# WIFI-NightLight-Infinity.net
KiCad netlist of a schematic drawn in EAGLE
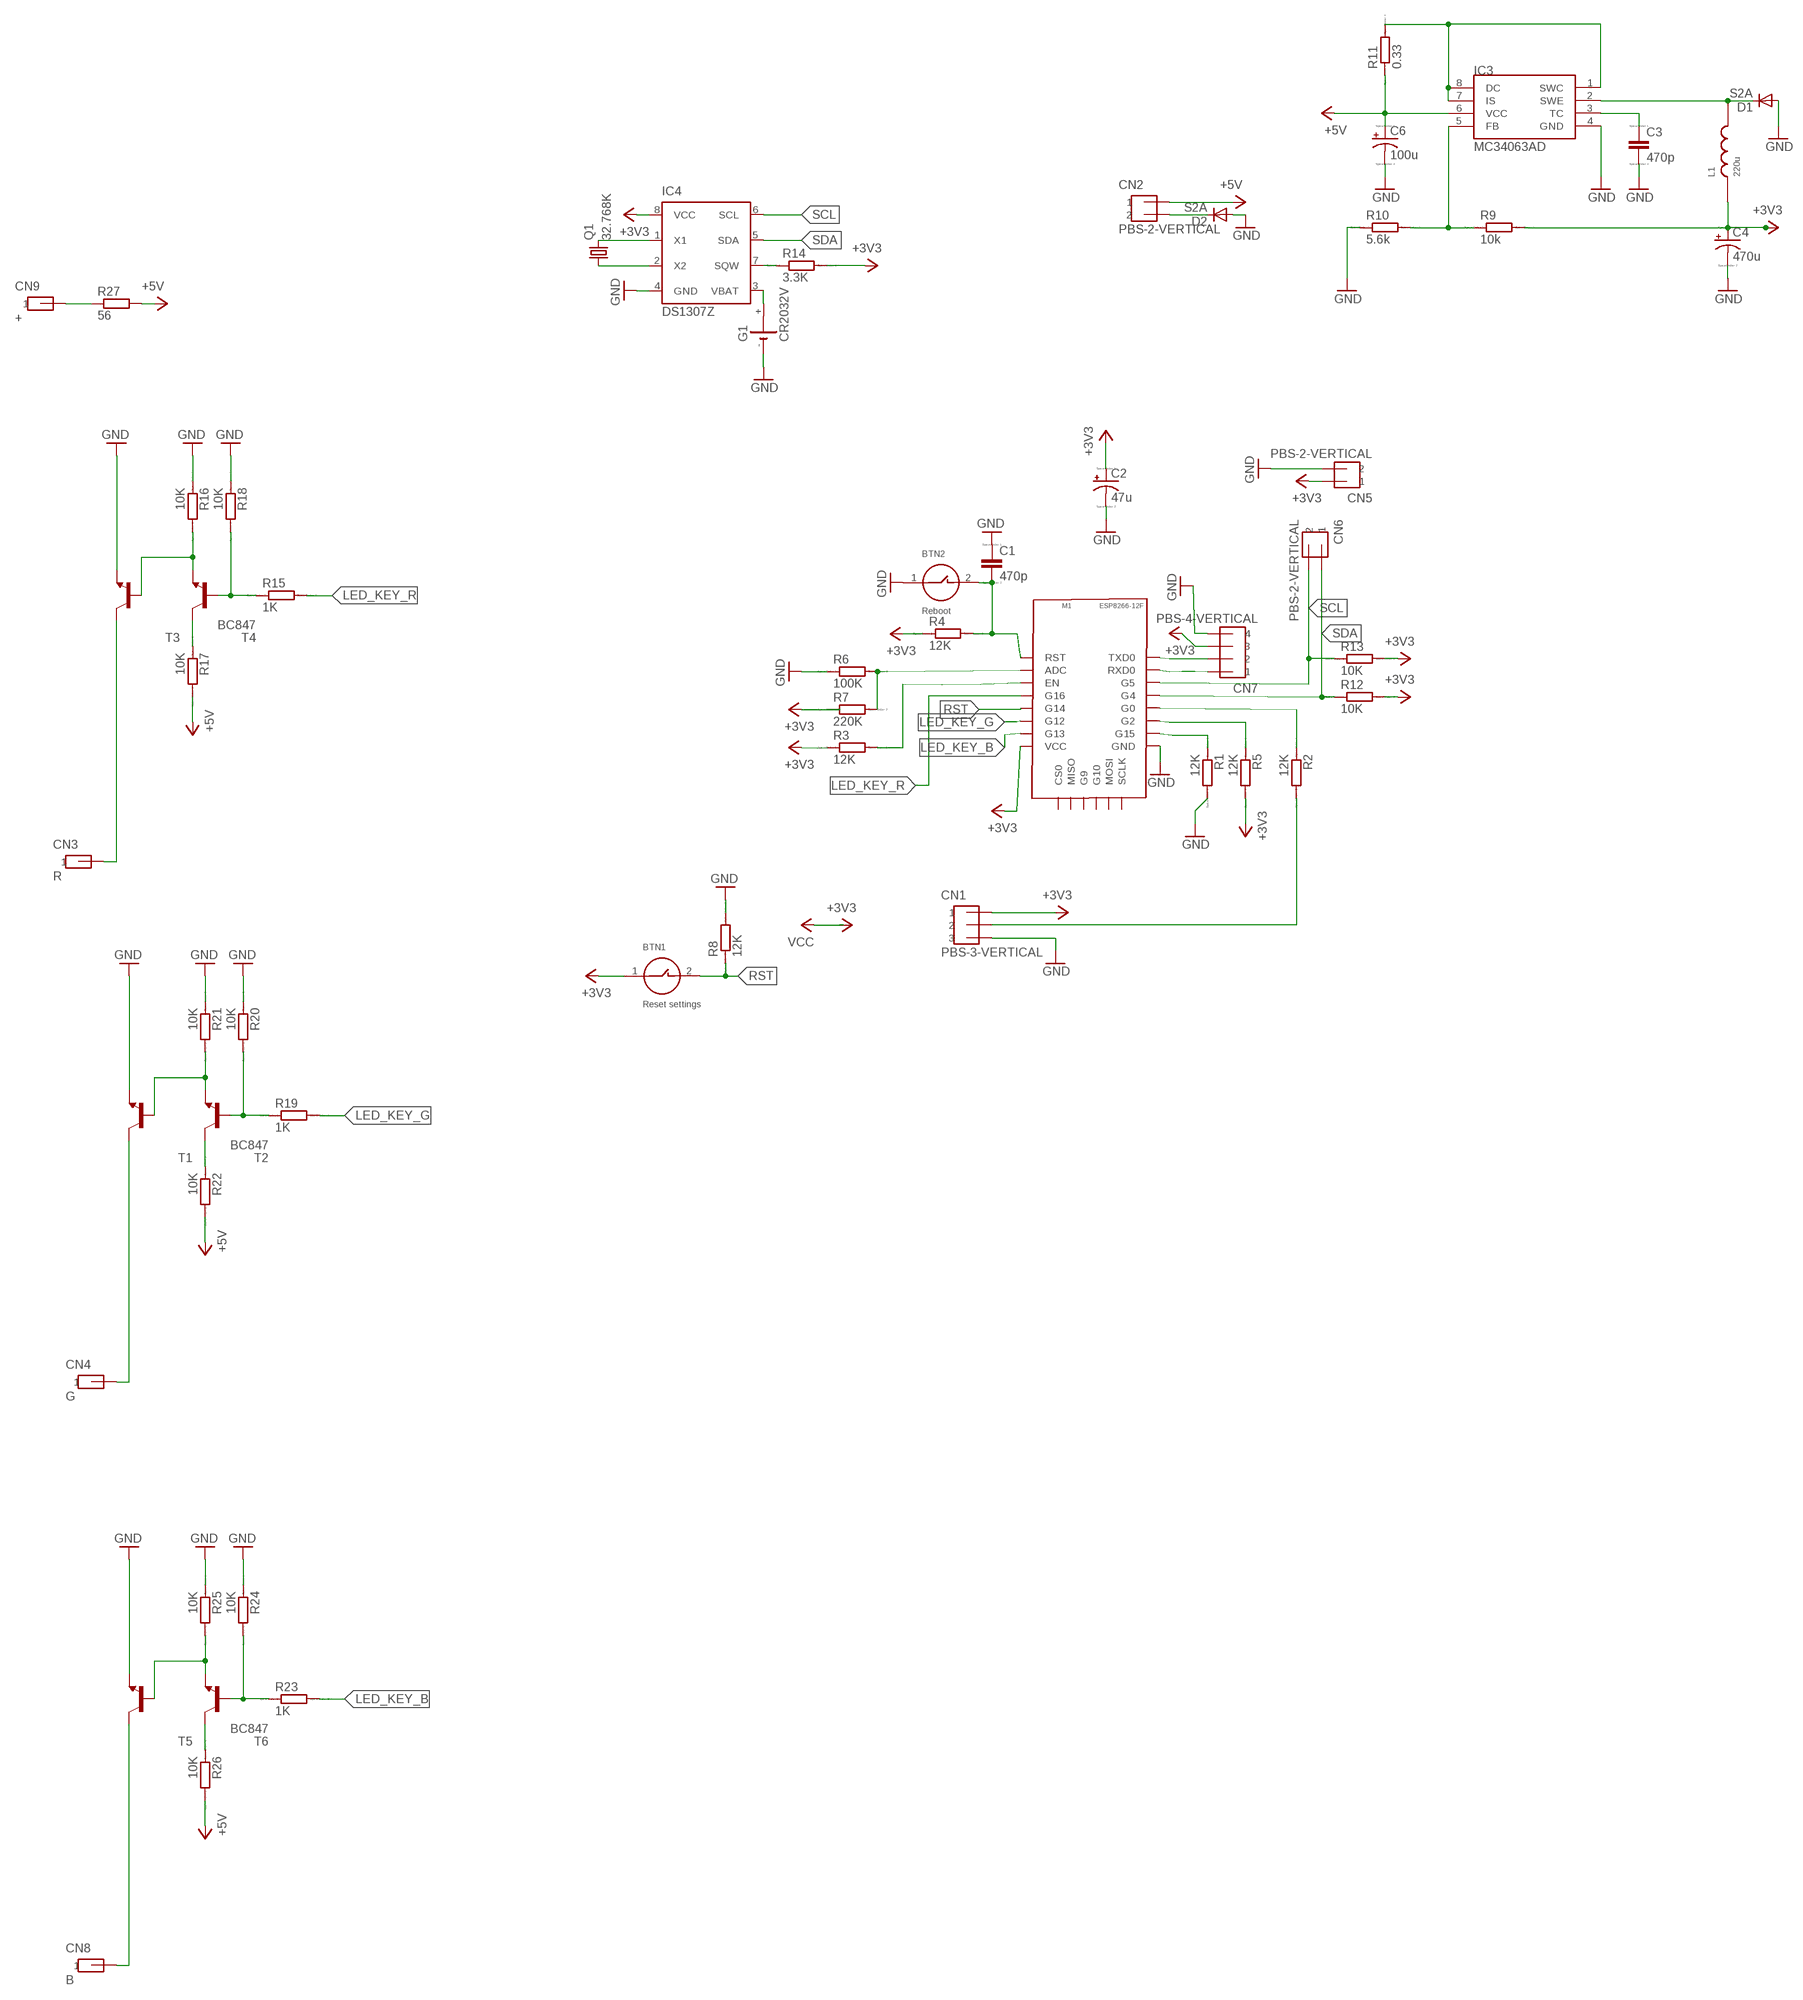
[diagram p0: schematic, sheet 1]

(export (version "E")
  (design (tool "Eeschema 10.0.6"))
  (components
    (comp (ref "BTN1")
      (value "Reset settings")
      (footprint "eagle-import:BTN-6X4-SMD")
      (libsource (lib "eagle-import") (part "BTN-6X4-SMD"))
    )
    (comp (ref "BTN2")
      (value "Reboot")
      (footprint "eagle-import:BTN-6X4-SMD")
      (libsource (lib "eagle-import") (part "BTN-6X4-SMD"))
    )
    (comp (ref "C1")
      (value "470p")
      (footprint "eagle-import:C0603")
      (libsource (lib "eagle-import") (part "CC0603"))
    )
    (comp (ref "C2")
      (value "47u")
      (footprint "eagle-import:CT3216")
      (libsource (lib "eagle-import") (part "CPOL-USCT3216"))
    )
    (comp (ref "C3")
      (value "470p")
      (footprint "eagle-import:C0603")
      (libsource (lib "eagle-import") (part "CC0603"))
    )
    (comp (ref "C4")
      (value "470u")
      (footprint "eagle-import:D_7343-31W")
      (libsource (lib "eagle-import") (part "CPOL-USD/7343-31W"))
    )
    (comp (ref "C6")
      (value "100u")
      (footprint "eagle-import:D_7343-31W")
      (libsource (lib "eagle-import") (part "CPOL-USD/7343-31W"))
    )
    (comp (ref "CN1")
      (value "PBS-3-VERTICAL")
      (footprint "eagle-import:PBS-3-VERTICAL")
      (libsource (lib "eagle-import") (part "PBS-3-VERTICAL"))
    )
    (comp (ref "CN2")
      (value "PBS-2-VERTICAL")
      (footprint "eagle-import:PBS-2-VERTICAL")
      (libsource (lib "eagle-import") (part "PBS-2-VERTICAL"))
    )
    (comp (ref "CN3")
      (value "R")
      (footprint "eagle-import:PBS-1-VERTICAL")
      (libsource (lib "eagle-import") (part "PBS-1-VERTICAL"))
    )
    (comp (ref "CN4")
      (value "G")
      (footprint "eagle-import:PBS-1-VERTICAL")
      (libsource (lib "eagle-import") (part "PBS-1-VERTICAL"))
    )
    (comp (ref "CN5")
      (value "PBS-2-VERTICAL")
      (footprint "eagle-import:PBS-2-VERTICAL")
      (libsource (lib "eagle-import") (part "PBS-2-VERTICAL"))
    )
    (comp (ref "CN6")
      (value "PBS-2-VERTICAL")
      (footprint "eagle-import:PBS-2-VERTICAL")
      (libsource (lib "eagle-import") (part "PBS-2-VERTICAL"))
    )
    (comp (ref "CN7")
      (value "PBS-4-VERTICAL")
      (footprint "eagle-import:PBS-4-VERTICAL")
      (libsource (lib "eagle-import") (part "PBS-4-VERTICAL"))
    )
    (comp (ref "CN8")
      (value "B")
      (footprint "eagle-import:PBS-1-VERTICAL")
      (libsource (lib "eagle-import") (part "PBS-1-VERTICAL"))
    )
    (comp (ref "CN9")
      (value "+")
      (footprint "eagle-import:PBS-1-VERTICAL")
      (libsource (lib "eagle-import") (part "PBS-1-VERTICAL"))
    )
    (comp (ref "D1")
      (value "S2A")
      (footprint "eagle-import:DO214AA")
      (fields (field (name "MF") "Fairchild"))
      (libsource (lib "eagle-import") (part "S2A"))
    )
    (comp (ref "D2")
      (value "S2A")
      (footprint "eagle-import:DO214AA")
      (fields (field (name "MF") "Fairchild"))
      (libsource (lib "eagle-import") (part "S2A"))
    )
    (comp (ref "G1")
      (value "CR2032V")
      (footprint "eagle-import:CR2032V")
      (libsource (lib "eagle-import") (part "CR2032V"))
    )
    (comp (ref "IC3")
      (value "MC34063AD")
      (footprint "eagle-import:SOIC8")
      (libsource (lib "eagle-import") (part "MC34063AD"))
    )
    (comp (ref "IC4")
      (value "DS1307Z")
      (footprint "eagle-import:SOIC8")
      (libsource (lib "eagle-import") (part "DS1307Z"))
    )
    (comp (ref "L1")
      (value "220u")
      (footprint "eagle-import:INDUCTOR-5-10")
      (libsource (lib "eagle-import") (part "INDUCTOR-5-10"))
    )
    (comp (ref "M1")
      (value "ESP8266-12F")
      (footprint "eagle-import:ESP8266-12F")
      (libsource (lib "eagle-import") (part "ESP8266-12F"))
    )
    (comp (ref "Q1")
      (value "32.768K")
      (footprint "eagle-import:TC38H")
      (libsource (lib "eagle-import") (part "CRYSTALTC38H"))
    )
    (comp (ref "R1")
      (value "12K")
      (footprint "eagle-import:R0603")
      (libsource (lib "eagle-import") (part "RR0603"))
    )
    (comp (ref "R2")
      (value "12K")
      (footprint "eagle-import:R0603")
      (libsource (lib "eagle-import") (part "RR0603"))
    )
    (comp (ref "R3")
      (value "12K")
      (footprint "eagle-import:R0603")
      (libsource (lib "eagle-import") (part "RR0603"))
    )
    (comp (ref "R4")
      (value "12K")
      (footprint "eagle-import:R0603")
      (libsource (lib "eagle-import") (part "RR0603"))
    )
    (comp (ref "R5")
      (value "12K")
      (footprint "eagle-import:R0603")
      (libsource (lib "eagle-import") (part "RR0603"))
    )
    (comp (ref "R6")
      (value "100K")
      (footprint "eagle-import:R0603")
      (libsource (lib "eagle-import") (part "RR0603"))
    )
    (comp (ref "R7")
      (value "220K")
      (footprint "eagle-import:R0603")
      (libsource (lib "eagle-import") (part "RR0603"))
    )
    (comp (ref "R8")
      (value "12K")
      (footprint "eagle-import:R0603")
      (libsource (lib "eagle-import") (part "RR0603"))
    )
    (comp (ref "R9")
      (value "10k")
      (footprint "eagle-import:R0603")
      (libsource (lib "eagle-import") (part "RR0603"))
    )
    (comp (ref "R10")
      (value "5.6k")
      (footprint "eagle-import:R0603")
      (libsource (lib "eagle-import") (part "RR0603"))
    )
    (comp (ref "R11")
      (value "0.33")
      (footprint "eagle-import:R0603")
      (libsource (lib "eagle-import") (part "RR0603"))
    )
    (comp (ref "R12")
      (value "10K")
      (footprint "eagle-import:R0603")
      (libsource (lib "eagle-import") (part "RR0603"))
    )
    (comp (ref "R13")
      (value "10K")
      (footprint "eagle-import:R0603")
      (libsource (lib "eagle-import") (part "RR0603"))
    )
    (comp (ref "R14")
      (value "3.3K")
      (footprint "eagle-import:R0603")
      (libsource (lib "eagle-import") (part "RR0603"))
    )
    (comp (ref "R15")
      (value "1K")
      (footprint "eagle-import:R0603")
      (libsource (lib "eagle-import") (part "RR0603"))
    )
    (comp (ref "R16")
      (value "10K")
      (footprint "eagle-import:R0603")
      (libsource (lib "eagle-import") (part "RR0603"))
    )
    (comp (ref "R17")
      (value "10K")
      (footprint "eagle-import:R0603")
      (libsource (lib "eagle-import") (part "RR0603"))
    )
    (comp (ref "R18")
      (value "10K")
      (footprint "eagle-import:R0603")
      (libsource (lib "eagle-import") (part "RR0603"))
    )
    (comp (ref "R19")
      (value "1K")
      (footprint "eagle-import:R0603")
      (libsource (lib "eagle-import") (part "RR0603"))
    )
    (comp (ref "R20")
      (value "10K")
      (footprint "eagle-import:R0603")
      (libsource (lib "eagle-import") (part "RR0603"))
    )
    (comp (ref "R21")
      (value "10K")
      (footprint "eagle-import:R0603")
      (libsource (lib "eagle-import") (part "RR0603"))
    )
    (comp (ref "R22")
      (value "10K")
      (footprint "eagle-import:R0603")
      (libsource (lib "eagle-import") (part "RR0603"))
    )
    (comp (ref "R23")
      (value "1K")
      (footprint "eagle-import:R0603")
      (libsource (lib "eagle-import") (part "RR0603"))
    )
    (comp (ref "R24")
      (value "10K")
      (footprint "eagle-import:R0603")
      (libsource (lib "eagle-import") (part "RR0603"))
    )
    (comp (ref "R25")
      (value "10K")
      (footprint "eagle-import:R0603")
      (libsource (lib "eagle-import") (part "RR0603"))
    )
    (comp (ref "R26")
      (value "10K")
      (footprint "eagle-import:R0603")
      (libsource (lib "eagle-import") (part "RR0603"))
    )
    (comp (ref "R27")
      (value "56")
      (footprint "eagle-import:0411_12")
      (libsource (lib "eagle-import") (part "R-EU_0411/12"))
    )
    (comp (ref "T1")
      (value "-NPN-TO126V")
      (footprint "eagle-import:TO126V")
      (libsource (lib "eagle-import") (part "-NPN-TO126V"))
    )
    (comp (ref "T2")
      (value "BC847")
      (footprint "eagle-import:SOT23")
      (libsource (lib "eagle-import") (part "BC847"))
    )
    (comp (ref "T3")
      (value "-NPN-TO126V")
      (footprint "eagle-import:TO126V")
      (libsource (lib "eagle-import") (part "-NPN-TO126V"))
    )
    (comp (ref "T4")
      (value "BC847")
      (footprint "eagle-import:SOT23")
      (libsource (lib "eagle-import") (part "BC847"))
    )
    (comp (ref "T5")
      (value "-NPN-TO126V")
      (footprint "eagle-import:TO126V")
      (libsource (lib "eagle-import") (part "-NPN-TO126V"))
    )
    (comp (ref "T6")
      (value "BC847")
      (footprint "eagle-import:SOT23")
      (libsource (lib "eagle-import") (part "BC847"))
    )
  )
  (nets
    (net (code "1") (name "+3V3") (class "Default")
      (node (ref "BTN1") (pin "1") (pinfunction "1_1") (pintype "bidirectional"))
      (node (ref "C2") (pin "-") (pinfunction "+_-") (pintype "passive"))
      (node (ref "C4") (pin "+") (pinfunction "+_+") (pintype "passive"))
      (node (ref "CN1") (pin "P$1") (pinfunction "1_P$1") (pintype "bidirectional"))
      (node (ref "CN5") (pin "P$1") (pinfunction "1_P$1") (pintype "bidirectional"))
      (node (ref "CN7") (pin "P$3") (pinfunction "3_P$3") (pintype "bidirectional"))
      (node (ref "IC4") (pin "8") (pinfunction "VCC_8") (pintype "power_in"))
      (node (ref "L1") (pin "P$1") (pinfunction "1_P$1") (pintype "bidirectional"))
      (node (ref "M1") (pin "VCC") (pinfunction "VCC_VCC") (pintype "power_in"))
      (node (ref "R12") (pin "2") (pinfunction "2_2") (pintype "passive"))
      (node (ref "R13") (pin "2") (pinfunction "2_2") (pintype "passive"))
      (node (ref "R14") (pin "2") (pinfunction "2_2") (pintype "passive"))
      (node (ref "R3") (pin "1") (pinfunction "1_1") (pintype "passive"))
      (node (ref "R4") (pin "1") (pinfunction "1_1") (pintype "passive"))
      (node (ref "R5") (pin "2") (pinfunction "2_2") (pintype "passive"))
      (node (ref "R7") (pin "1") (pinfunction "1_1") (pintype "passive"))
      (node (ref "R9") (pin "2") (pinfunction "2_2") (pintype "passive"))
    )
    (net (code "2") (name "+5V") (class "Default")
      (node (ref "C6") (pin "+") (pinfunction "+_+") (pintype "passive"))
      (node (ref "CN2") (pin "P$1") (pinfunction "1_P$1") (pintype "bidirectional"))
      (node (ref "IC3") (pin "6") (pinfunction "VCC_6") (pintype "passive"))
      (node (ref "R11") (pin "1") (pinfunction "1_1") (pintype "passive"))
      (node (ref "R17") (pin "2") (pinfunction "2_2") (pintype "passive"))
      (node (ref "R22") (pin "2") (pinfunction "2_2") (pintype "passive"))
      (node (ref "R26") (pin "2") (pinfunction "2_2") (pintype "passive"))
      (node (ref "R27") (pin "2") (pinfunction "2_2") (pintype "passive"))
    )
    (net (code "3") (name "/N$24") (class "Default")
      (node (ref "BTN2") (pin "2") (pinfunction "2_2") (pintype "bidirectional"))
      (node (ref "C1") (pin "2") (pinfunction "2_2") (pintype "passive"))
      (node (ref "M1") (pin "RST") (pinfunction "RST_RST") (pintype "bidirectional"))
      (node (ref "R4") (pin "2") (pinfunction "2_2") (pintype "passive"))
    )
    (net (code "4") (name "GND") (class "Default")
      (node (ref "BTN2") (pin "1") (pinfunction "1_1") (pintype "bidirectional"))
      (node (ref "C1") (pin "1") (pinfunction "1_1") (pintype "passive"))
      (node (ref "C2") (pin "+") (pinfunction "-_+") (pintype "passive"))
      (node (ref "C3") (pin "2") (pinfunction "2_2") (pintype "passive"))
      (node (ref "C4") (pin "-") (pinfunction "-_-") (pintype "passive"))
      (node (ref "C6") (pin "-") (pinfunction "-_-") (pintype "passive"))
      (node (ref "CN1") (pin "P$3") (pinfunction "3_P$3") (pintype "bidirectional"))
      (node (ref "CN5") (pin "P$2") (pinfunction "2_P$2") (pintype "bidirectional"))
      (node (ref "CN7") (pin "P$4") (pinfunction "4_P$4") (pintype "bidirectional"))
      (node (ref "D1") (pin "A") (pinfunction "A_A") (pintype "passive"))
      (node (ref "D2") (pin "A") (pinfunction "A_A") (pintype "passive"))
      (node (ref "G1") (pin "-") (pinfunction "-_-") (pintype "passive"))
      (node (ref "IC3") (pin "4") (pinfunction "GND_4") (pintype "passive"))
      (node (ref "IC4") (pin "4") (pinfunction "GND_4") (pintype "power_in"))
      (node (ref "M1") (pin "GND") (pinfunction "GND_GND") (pintype "power_in"))
      (node (ref "R1") (pin "2") (pinfunction "2_2") (pintype "passive"))
      (node (ref "R10") (pin "1") (pinfunction "1_1") (pintype "passive"))
      (node (ref "R16") (pin "1") (pinfunction "1_1") (pintype "passive"))
      (node (ref "R18") (pin "1") (pinfunction "1_1") (pintype "passive"))
      (node (ref "R20") (pin "1") (pinfunction "1_1") (pintype "passive"))
      (node (ref "R21") (pin "1") (pinfunction "1_1") (pintype "passive"))
      (node (ref "R24") (pin "1") (pinfunction "1_1") (pintype "passive"))
      (node (ref "R25") (pin "1") (pinfunction "1_1") (pintype "passive"))
      (node (ref "R6") (pin "1") (pinfunction "1_1") (pintype "passive"))
      (node (ref "R8") (pin "2") (pinfunction "2_2") (pintype "passive"))
      (node (ref "T1") (pin "1") (pinfunction "E_1") (pintype "passive"))
      (node (ref "T3") (pin "1") (pinfunction "E_1") (pintype "passive"))
      (node (ref "T5") (pin "1") (pinfunction "E_1") (pintype "passive"))
    )
    (net (code "5") (name "LED_KEY_B") (class "Default")
      (node (ref "M1") (pin "G13") (pinfunction "G13_G13") (pintype "bidirectional"))
      (node (ref "R23") (pin "2") (pinfunction "2_2") (pintype "passive"))
    )
    (net (code "6") (name "LED_KEY_G") (class "Default")
      (node (ref "M1") (pin "G12") (pinfunction "G12_G12") (pintype "bidirectional"))
      (node (ref "R19") (pin "2") (pinfunction "2_2") (pintype "passive"))
    )
    (net (code "7") (name "LED_KEY_R") (class "Default")
      (node (ref "M1") (pin "G16") (pinfunction "G16_G16") (pintype "bidirectional"))
      (node (ref "R15") (pin "2") (pinfunction "2_2") (pintype "passive"))
    )
    (net (code "8") (name "Net-(CN1-2)") (class "Default")
      (node (ref "CN1") (pin "P$2") (pinfunction "2_P$2") (pintype "bidirectional"))
      (node (ref "R2") (pin "2") (pinfunction "2_2") (pintype "passive"))
    )
    (net (code "9") (name "Net-(CN2-2)") (class "Default")
      (node (ref "CN2") (pin "P$2") (pinfunction "2_P$2") (pintype "bidirectional"))
      (node (ref "D2") (pin "C") (pinfunction "C_C") (pintype "passive"))
    )
    (net (code "10") (name "Net-(CN3-1)") (class "Default")
      (node (ref "CN3") (pin "P$1") (pinfunction "1_P$1") (pintype "bidirectional"))
      (node (ref "T3") (pin "2") (pinfunction "C_2") (pintype "passive"))
    )
    (net (code "11") (name "Net-(CN4-1)") (class "Default")
      (node (ref "CN4") (pin "P$1") (pinfunction "1_P$1") (pintype "bidirectional"))
      (node (ref "T1") (pin "2") (pinfunction "C_2") (pintype "passive"))
    )
    (net (code "12") (name "Net-(CN7-1)") (class "Default")
      (node (ref "CN7") (pin "P$1") (pinfunction "1_P$1") (pintype "bidirectional"))
      (node (ref "M1") (pin "RXD0") (pinfunction "RXD0_RXD0") (pintype "bidirectional"))
    )
    (net (code "13") (name "Net-(CN7-2)") (class "Default")
      (node (ref "CN7") (pin "P$2") (pinfunction "2_P$2") (pintype "bidirectional"))
      (node (ref "M1") (pin "TXD0") (pinfunction "TXD0_TXD0") (pintype "bidirectional"))
    )
    (net (code "14") (name "Net-(CN8-1)") (class "Default")
      (node (ref "CN8") (pin "P$1") (pinfunction "1_P$1") (pintype "bidirectional"))
      (node (ref "T5") (pin "2") (pinfunction "C_2") (pintype "passive"))
    )
    (net (code "15") (name "Net-(CN9-1)") (class "Default")
      (node (ref "CN9") (pin "P$1") (pinfunction "1_P$1") (pintype "bidirectional"))
      (node (ref "R27") (pin "1") (pinfunction "1_1") (pintype "passive"))
    )
    (net (code "16") (name "Net-(IC3-DC)") (class "Default")
      (node (ref "IC3") (pin "1") (pinfunction "SWC_1") (pintype "passive"))
      (node (ref "IC3") (pin "7") (pinfunction "IS_7") (pintype "passive"))
      (node (ref "IC3") (pin "8") (pinfunction "DC_8") (pintype "passive"))
      (node (ref "R11") (pin "2") (pinfunction "2_2") (pintype "passive"))
    )
    (net (code "17") (name "Net-(IC3-FB)") (class "Default")
      (node (ref "IC3") (pin "5") (pinfunction "FB_5") (pintype "passive"))
      (node (ref "R10") (pin "2") (pinfunction "2_2") (pintype "passive"))
      (node (ref "R9") (pin "1") (pinfunction "1_1") (pintype "passive"))
    )
    (net (code "18") (name "Net-(IC3-SWE)") (class "Default")
      (node (ref "D1") (pin "C") (pinfunction "C_C") (pintype "passive"))
      (node (ref "IC3") (pin "2") (pinfunction "SWE_2") (pintype "passive"))
      (node (ref "L1") (pin "P$2") (pinfunction "P$2_P$2") (pintype "bidirectional"))
    )
    (net (code "19") (name "Net-(IC3-TC)") (class "Default")
      (node (ref "C3") (pin "1") (pinfunction "1_1") (pintype "passive"))
      (node (ref "IC3") (pin "3") (pinfunction "TC_3") (pintype "passive"))
    )
    (net (code "20") (name "Net-(IC4-SQW)") (class "Default")
      (node (ref "IC4") (pin "7") (pinfunction "SQW_7") (pintype "open_collector"))
      (node (ref "R14") (pin "1") (pinfunction "1_1") (pintype "passive"))
    )
    (net (code "21") (name "Net-(IC4-VBAT)") (class "Default")
      (node (ref "G1") (pin "+") (pinfunction "+_+") (pintype "passive"))
      (node (ref "IC4") (pin "3") (pinfunction "VBAT_3") (pintype "passive"))
    )
    (net (code "22") (name "Net-(IC4-X1)") (class "Default")
      (node (ref "IC4") (pin "1") (pinfunction "X1_1") (pintype "input"))
      (node (ref "Q1") (pin "2") (pinfunction "2_2") (pintype "passive"))
    )
    (net (code "23") (name "Net-(IC4-X2)") (class "Default")
      (node (ref "IC4") (pin "2") (pinfunction "X2_2") (pintype "output"))
      (node (ref "Q1") (pin "1") (pinfunction "1_1") (pintype "passive"))
    )
    (net (code "24") (name "Net-(M1-PadADC)") (class "Default")
      (node (ref "M1") (pin "ADC") (pinfunction "ADC_ADC") (pintype "bidirectional"))
      (node (ref "R6") (pin "2") (pinfunction "2_2") (pintype "passive"))
      (node (ref "R7") (pin "2") (pinfunction "2_2") (pintype "passive"))
    )
    (net (code "25") (name "Net-(M1-PadEN)") (class "Default")
      (node (ref "M1") (pin "EN") (pinfunction "EN_EN") (pintype "bidirectional"))
      (node (ref "R3") (pin "2") (pinfunction "2_2") (pintype "passive"))
    )
    (net (code "26") (name "Net-(M1-PadG0)") (class "Default")
      (node (ref "M1") (pin "G0") (pinfunction "G0_G0") (pintype "bidirectional"))
      (node (ref "R2") (pin "1") (pinfunction "1_1") (pintype "passive"))
    )
    (net (code "27") (name "Net-(M1-PadG2)") (class "Default")
      (node (ref "M1") (pin "G2") (pinfunction "G2_G2") (pintype "bidirectional"))
      (node (ref "R5") (pin "1") (pinfunction "1_1") (pintype "passive"))
    )
    (net (code "28") (name "Net-(M1-PadG15)") (class "Default")
      (node (ref "M1") (pin "G15") (pinfunction "G15_G15") (pintype "bidirectional"))
      (node (ref "R1") (pin "1") (pinfunction "1_1") (pintype "passive"))
    )
    (net (code "29") (name "Net-(T1-B)") (class "Default")
      (node (ref "R21") (pin "2") (pinfunction "2_2") (pintype "passive"))
      (node (ref "T1") (pin "3") (pinfunction "B_3") (pintype "passive"))
      (node (ref "T2") (pin "2") (pinfunction "E_2") (pintype "passive"))
    )
    (net (code "30") (name "Net-(T2-B)") (class "Default")
      (node (ref "R19") (pin "1") (pinfunction "1_1") (pintype "passive"))
      (node (ref "R20") (pin "2") (pinfunction "2_2") (pintype "passive"))
      (node (ref "T2") (pin "1") (pinfunction "B_1") (pintype "passive"))
    )
    (net (code "31") (name "Net-(T2-C)") (class "Default")
      (node (ref "R22") (pin "1") (pinfunction "1_1") (pintype "passive"))
      (node (ref "T2") (pin "3") (pinfunction "C_3") (pintype "passive"))
    )
    (net (code "32") (name "Net-(T3-B)") (class "Default")
      (node (ref "R16") (pin "2") (pinfunction "2_2") (pintype "passive"))
      (node (ref "T3") (pin "3") (pinfunction "B_3") (pintype "passive"))
      (node (ref "T4") (pin "2") (pinfunction "E_2") (pintype "passive"))
    )
    (net (code "33") (name "Net-(T4-B)") (class "Default")
      (node (ref "R15") (pin "1") (pinfunction "1_1") (pintype "passive"))
      (node (ref "R18") (pin "2") (pinfunction "2_2") (pintype "passive"))
      (node (ref "T4") (pin "1") (pinfunction "B_1") (pintype "passive"))
    )
    (net (code "34") (name "Net-(T4-C)") (class "Default")
      (node (ref "R17") (pin "1") (pinfunction "1_1") (pintype "passive"))
      (node (ref "T4") (pin "3") (pinfunction "C_3") (pintype "passive"))
    )
    (net (code "35") (name "Net-(T5-B)") (class "Default")
      (node (ref "R25") (pin "2") (pinfunction "2_2") (pintype "passive"))
      (node (ref "T5") (pin "3") (pinfunction "B_3") (pintype "passive"))
      (node (ref "T6") (pin "2") (pinfunction "E_2") (pintype "passive"))
    )
    (net (code "36") (name "Net-(T6-B)") (class "Default")
      (node (ref "R23") (pin "1") (pinfunction "1_1") (pintype "passive"))
      (node (ref "R24") (pin "2") (pinfunction "2_2") (pintype "passive"))
      (node (ref "T6") (pin "1") (pinfunction "B_1") (pintype "passive"))
    )
    (net (code "37") (name "Net-(T6-C)") (class "Default")
      (node (ref "R26") (pin "1") (pinfunction "1_1") (pintype "passive"))
      (node (ref "T6") (pin "3") (pinfunction "C_3") (pintype "passive"))
    )
    (net (code "38") (name "RST") (class "Default")
      (node (ref "BTN1") (pin "2") (pinfunction "2_2") (pintype "bidirectional"))
      (node (ref "M1") (pin "G14") (pinfunction "G14_G14") (pintype "bidirectional"))
      (node (ref "R8") (pin "1") (pinfunction "1_1") (pintype "passive"))
    )
    (net (code "39") (name "SCL") (class "Default")
      (node (ref "CN6") (pin "P$2") (pinfunction "2_P$2") (pintype "bidirectional"))
      (node (ref "IC4") (pin "6") (pinfunction "SCL_6") (pintype "input"))
      (node (ref "M1") (pin "G5") (pinfunction "G5_G5") (pintype "bidirectional"))
      (node (ref "R13") (pin "1") (pinfunction "1_1") (pintype "passive"))
    )
    (net (code "40") (name "SDA") (class "Default")
      (node (ref "CN6") (pin "P$1") (pinfunction "1_P$1") (pintype "bidirectional"))
      (node (ref "IC4") (pin "5") (pinfunction "SDA_5") (pintype "bidirectional"))
      (node (ref "M1") (pin "G4") (pinfunction "G4_G4") (pintype "bidirectional"))
      (node (ref "R12") (pin "1") (pinfunction "1_1") (pintype "passive"))
    )
    (net (code "41") (name "unconnected-(G1-+-Pad+@1)") (class "Default")
      (node (ref "G1") (pin "+@1") (pinfunction "+_+@1") (pintype "passive"))
    )
    (net (code "42") (name "unconnected-(M1-PadCS0)") (class "Default")
      (node (ref "M1") (pin "CS0") (pinfunction "CS0_CS0") (pintype "bidirectional"))
    )
    (net (code "43") (name "unconnected-(M1-PadG9)") (class "Default")
      (node (ref "M1") (pin "G9") (pinfunction "G9_G9") (pintype "bidirectional"))
    )
    (net (code "44") (name "unconnected-(M1-PadG10)") (class "Default")
      (node (ref "M1") (pin "G10") (pinfunction "G10_G10") (pintype "bidirectional"))
    )
    (net (code "45") (name "unconnected-(M1-PadMISO)") (class "Default")
      (node (ref "M1") (pin "MISO") (pinfunction "MISO_MISO") (pintype "bidirectional"))
    )
    (net (code "46") (name "unconnected-(M1-PadMOSI)") (class "Default")
      (node (ref "M1") (pin "MOSI") (pinfunction "MOSI_MOSI") (pintype "bidirectional"))
    )
    (net (code "47") (name "unconnected-(M1-PadSCLK)") (class "Default")
      (node (ref "M1") (pin "SCLK") (pinfunction "SCLK_SCLK") (pintype "bidirectional"))
    )
  )
)
